# Button.net
KiCad netlist of a schematic drawn in Altium Designer
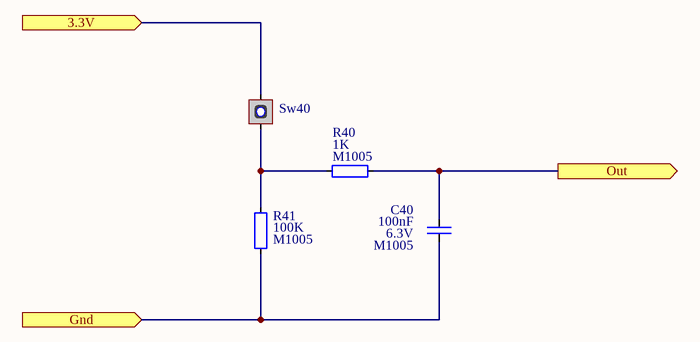
[diagram p0: Button.SchDoc]

(export (version "E")
  (design (tool "Eeschema 10.0.6"))
  (components
    (comp (ref "C40")
      (value "100nF")
      (footprint "Capacitor_Ceramic_M1005_I0402")
      (description "Cap, Cer, 100nF, 6.3V, M1005")
      (fields
        (field (name "VOLTAGE") "6.3V")
        (field (name "MANUFACTURER PART NUMBER") "04026D104KAT4A")
        (field (name "MANUFACTURER") "Kyocera")
        (field (name "PACKAGE") "M1005")
      )
      (libsource (lib "Capacitor") (part "Capacitor_Ceramic"))
    )
    (comp (ref "R40")
      (value "1K")
      (footprint "Resistor_Smd_M1005_I0402")
      (description "Res, 1K, 1%, M1005")
      (fields
        (field (name "TOLERANCE") "1%")
        (field (name "MANUFACTURER") "Yageo")
        (field (name "PACKAGE") "M1005")
      )
      (libsource (lib "Resistor") (part "Resistor"))
    )
    (comp (ref "R41")
      (value "100K")
      (footprint "Resistor_Smd_M1005_I0402")
      (description "Res, 100K, 1%, M1005")
      (fields
        (field (name "TOLERANCE") "1%")
        (field (name "MANUFACTURER") "Yageo")
        (field (name "PACKAGE") "M1005")
      )
      (libsource (lib "Resistor") (part "Resistor"))
    )
    (comp (ref "Sw40")
      (value "Tactile, SPST")
      (footprint "Tactile, SPST - Panasonic, EVQQ2")
      (description "Switch, Tactile, SPST, SMD")
      (fields
        (field (name "MANUFACTURER") "Panasonic")
        (field (name "MANUFACTURER PART NUMBER") "EVQ-Q2K03W")
      )
      (libsource (lib "Switch") (part "Tactile, SPST"))
    )
  )
  (nets
    (net (code "1") (name "/3.3V") (class "Default")
      (node (ref "Sw40") (pin "A") (pinfunction "A_A") (pintype "passive"))
    )
    (net (code "2") (name "/Gnd") (class "Default")
      (node (ref "C40") (pin "2") (pinfunction "2_2") (pintype "passive"))
      (node (ref "R41") (pin "2") (pinfunction "2_2") (pintype "passive"))
    )
    (net (code "3") (name "/Out") (class "Default")
      (node (ref "C40") (pin "1") (pinfunction "1_1") (pintype "passive"))
      (node (ref "R40") (pin "2") (pinfunction "2_2") (pintype "passive"))
    )
    (net (code "4") (name "Net-(R40-Pad1)") (class "Default")
      (node (ref "R40") (pin "1") (pinfunction "1_1") (pintype "passive"))
      (node (ref "R41") (pin "1") (pinfunction "1_1") (pintype "passive"))
      (node (ref "Sw40") (pin "B") (pinfunction "B_B") (pintype "passive"))
    )
  )
)
